# WiFiNode_CPU2_R00.net
KiCad netlist of a schematic drawn in Altium Designer
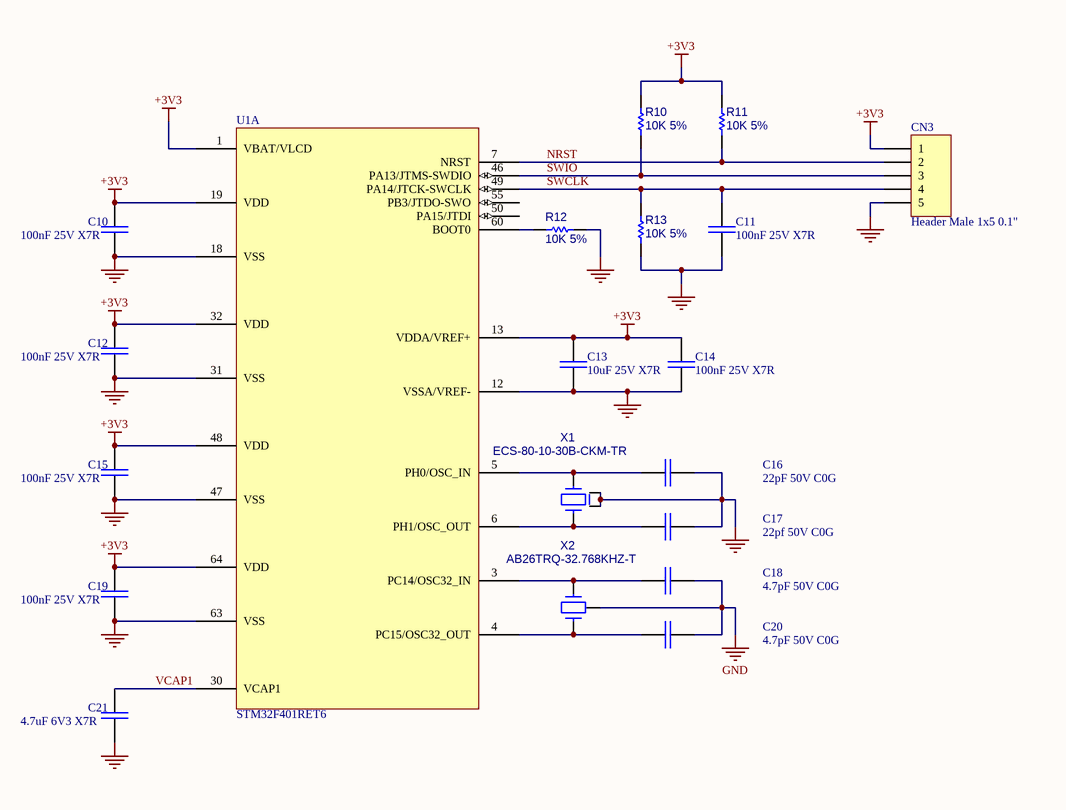
[diagram p0: WiFiNode_CPU2_R00.SchDoc]

(export (version "E")
  (design (tool "Eeschema 10.0.6"))
  (components
    (comp (ref "C10")
      (value "100nF 25V X7R")
      (footprint "C_0805")
      (description "Ceramic Capacitor")
      (libsource (lib "WiFiNode_R00") (part "Ceramic capacitor"))
    )
    (comp (ref "C11")
      (value "100nF 25V X7R")
      (footprint "C_0805")
      (description "Ceramic Capacitor")
      (libsource (lib "WiFiNode_R00") (part "Ceramic capacitor"))
    )
    (comp (ref "C12")
      (value "100nF 25V X7R")
      (footprint "C_0805")
      (description "Ceramic Capacitor")
      (libsource (lib "WiFiNode_R00") (part "Ceramic capacitor"))
    )
    (comp (ref "C13")
      (value "10uF 25V X7R")
      (footprint "C_0805")
      (description "Ceramic Capacitor")
      (libsource (lib "WiFiNode_R00") (part "Ceramic capacitor"))
    )
    (comp (ref "C14")
      (value "100nF 25V X7R")
      (footprint "C_0805")
      (description "Ceramic Capacitor")
      (libsource (lib "WiFiNode_R00") (part "Ceramic capacitor"))
    )
    (comp (ref "C15")
      (value "100nF 25V X7R")
      (footprint "C_0805")
      (description "Ceramic Capacitor")
      (libsource (lib "WiFiNode_R00") (part "Ceramic capacitor"))
    )
    (comp (ref "C16")
      (value "22pF 50V C0G")
      (footprint "C_0805")
      (description "Ceramic Capacitor")
      (libsource (lib "WiFiNode_R00") (part "Ceramic capacitor"))
    )
    (comp (ref "C17")
      (value "22pf 50V C0G")
      (footprint "C_0805")
      (description "Ceramic Capacitor")
      (libsource (lib "WiFiNode_R00") (part "Ceramic capacitor"))
    )
    (comp (ref "C18")
      (value "4.7pF 50V C0G")
      (footprint "C_0805")
      (description "Ceramic Capacitor")
      (libsource (lib "WiFiNode_R00") (part "Ceramic capacitor"))
    )
    (comp (ref "C19")
      (value "100nF 25V X7R")
      (footprint "C_0805")
      (description "Ceramic Capacitor")
      (libsource (lib "WiFiNode_R00") (part "Ceramic capacitor"))
    )
    (comp (ref "C20")
      (value "4.7pF 50V C0G")
      (footprint "C_0805")
      (description "Ceramic Capacitor")
      (libsource (lib "WiFiNode_R00") (part "Ceramic capacitor"))
    )
    (comp (ref "C21")
      (value "4.7uF 6V3 X7R")
      (footprint "C_0805")
      (description "Ceramic Capacitor")
      (libsource (lib "WiFiNode_R00") (part "Ceramic capacitor"))
    )
    (comp (ref "CN3")
      (value "Header Male 1x5 0.1\"")
      (footprint "Header_M_1x5_0.1\"")
      (description "Connector Generic 5 Vias")
      (libsource (lib "WiFiNode_R00") (part "CONN_05P"))
    )
    (comp (ref "R10")
      (value "10K 5%")
      (footprint "R_0805")
      (description "Resistor")
      (libsource (lib "WiFiNode_R00") (part "Res1"))
    )
    (comp (ref "R11")
      (value "10K 5%")
      (footprint "R_0805")
      (description "Resistor")
      (libsource (lib "WiFiNode_R00") (part "Res1"))
    )
    (comp (ref "R12")
      (value "10K 5%")
      (footprint "R_0805")
      (description "Resistor")
      (libsource (lib "WiFiNode_R00") (part "Res1"))
    )
    (comp (ref "R13")
      (value "10K 5%")
      (footprint "R_0805")
      (description "Resistor")
      (libsource (lib "WiFiNode_R00") (part "Res1"))
    )
    (comp (ref "U1")
      (value "STM32F401RET6")
      (footprint "LQFP_64")
      (libsource (lib "WiFiNode_R00") (part "STM32F401RE"))
    )
    (comp (ref "X1")
      (value "ECS-80-10-30B-CKM-TR")
      (footprint "ABM3C")
      (description "Crystal 4 Vias + GND")
      (libsource (lib "WiFiNode_R00") (part "CRYSTAL_4P"))
    )
    (comp (ref "X2")
      (value "AB26TRQ-32.768KHZ-T")
      (footprint "AB26TQF")
      (description "Crystal 2 Vias + GND")
      (libsource (lib "WiFiNode_R00") (part "CRYSTAL 3P"))
    )
  )
  (nets
    (net (code "1") (name "+3V3") (class "Default")
      (node (ref "C10") (pin "1") (pinfunction "1_1") (pintype "passive"))
      (node (ref "C12") (pin "1") (pinfunction "1_1") (pintype "passive"))
      (node (ref "C13") (pin "1") (pinfunction "1_1") (pintype "passive"))
      (node (ref "C14") (pin "1") (pinfunction "1_1") (pintype "passive"))
      (node (ref "C15") (pin "1") (pinfunction "1_1") (pintype "passive"))
      (node (ref "C19") (pin "1") (pinfunction "1_1") (pintype "passive"))
      (node (ref "CN3") (pin "1") (pinfunction "1_1") (pintype "passive"))
      (node (ref "R10") (pin "1") (pinfunction "1_1") (pintype "passive"))
      (node (ref "R11") (pin "1") (pinfunction "1_1") (pintype "passive"))
      (node (ref "U1") (pin "1") (pinfunction "VBAT/VLCD_1") (pintype "passive"))
      (node (ref "U1") (pin "13") (pinfunction "VDDA/VREF+_13") (pintype "passive"))
      (node (ref "U1") (pin "19") (pinfunction "VDD_19") (pintype "passive"))
      (node (ref "U1") (pin "32") (pinfunction "VDD_32") (pintype "passive"))
      (node (ref "U1") (pin "48") (pinfunction "VDD_48") (pintype "passive"))
      (node (ref "U1") (pin "64") (pinfunction "VDD_64") (pintype "passive"))
    )
    (net (code "2") (name "/NRST") (class "Default")
      (node (ref "CN3") (pin "2") (pinfunction "2_2") (pintype "passive"))
      (node (ref "R11") (pin "2") (pinfunction "2_2") (pintype "passive"))
      (node (ref "U1") (pin "7") (pinfunction "NRST_7") (pintype "passive"))
    )
    (net (code "3") (name "/SWCLK") (class "Default")
      (node (ref "C11") (pin "1") (pinfunction "1_1") (pintype "passive"))
      (node (ref "CN3") (pin "4") (pinfunction "4_4") (pintype "passive"))
      (node (ref "R13") (pin "1") (pinfunction "1_1") (pintype "passive"))
      (node (ref "U1") (pin "49") (pinfunction "PA14/JTCK-SWCLK_49") (pintype "bidirectional"))
    )
    (net (code "4") (name "/SWIO") (class "Default")
      (node (ref "CN3") (pin "3") (pinfunction "3_3") (pintype "passive"))
      (node (ref "R10") (pin "2") (pinfunction "2_2") (pintype "passive"))
      (node (ref "U1") (pin "46") (pinfunction "PA13/JTMS-SWDIO_46") (pintype "bidirectional"))
    )
    (net (code "5") (name "/VCAP1") (class "Default")
      (node (ref "C21") (pin "1") (pinfunction "1_1") (pintype "passive"))
      (node (ref "U1") (pin "30") (pinfunction "VCAP1_30") (pintype "passive"))
    )
    (net (code "6") (name "GND") (class "Default")
      (node (ref "C10") (pin "2") (pinfunction "2_2") (pintype "passive"))
      (node (ref "C11") (pin "2") (pinfunction "2_2") (pintype "passive"))
      (node (ref "C12") (pin "2") (pinfunction "2_2") (pintype "passive"))
      (node (ref "C13") (pin "2") (pinfunction "2_2") (pintype "passive"))
      (node (ref "C14") (pin "2") (pinfunction "2_2") (pintype "passive"))
      (node (ref "C15") (pin "2") (pinfunction "2_2") (pintype "passive"))
      (node (ref "C16") (pin "2") (pinfunction "2_2") (pintype "passive"))
      (node (ref "C17") (pin "2") (pinfunction "2_2") (pintype "passive"))
      (node (ref "C18") (pin "2") (pinfunction "2_2") (pintype "passive"))
      (node (ref "C19") (pin "2") (pinfunction "2_2") (pintype "passive"))
      (node (ref "C20") (pin "2") (pinfunction "2_2") (pintype "passive"))
      (node (ref "C21") (pin "2") (pinfunction "2_2") (pintype "passive"))
      (node (ref "CN3") (pin "5") (pinfunction "5_5") (pintype "passive"))
      (node (ref "R12") (pin "1") (pinfunction "1_1") (pintype "passive"))
      (node (ref "R13") (pin "2") (pinfunction "2_2") (pintype "passive"))
      (node (ref "U1") (pin "12") (pinfunction "VSSA/VREF-_12") (pintype "passive"))
      (node (ref "U1") (pin "18") (pinfunction "VSS_18") (pintype "passive"))
      (node (ref "U1") (pin "31") (pinfunction "VSS_31") (pintype "passive"))
      (node (ref "U1") (pin "47") (pinfunction "VSS_47") (pintype "passive"))
      (node (ref "U1") (pin "63") (pinfunction "VSS_63") (pintype "passive"))
      (node (ref "X1") (pin "2") (pinfunction "2_2") (pintype "passive"))
      (node (ref "X1") (pin "4") (pinfunction "4_4") (pintype "passive"))
      (node (ref "X2") (pin "3") (pinfunction "3_3") (pintype "passive"))
    )
    (net (code "7") (name "Net-(U1A-BOOT0)") (class "Default")
      (node (ref "R12") (pin "2") (pinfunction "2_2") (pintype "passive"))
      (node (ref "U1") (pin "60") (pinfunction "BOOT0_60") (pintype "passive"))
    )
    (net (code "8") (name "Net-(U1A-PC14{slash}OSC32_IN)") (class "Default")
      (node (ref "C18") (pin "1") (pinfunction "1_1") (pintype "passive"))
      (node (ref "U1") (pin "3") (pinfunction "PC14/OSC32_IN_3") (pintype "passive"))
      (node (ref "X2") (pin "2") (pinfunction "2_2") (pintype "passive"))
    )
    (net (code "9") (name "Net-(U1A-PC15{slash}OSC32_OUT)") (class "Default")
      (node (ref "C20") (pin "1") (pinfunction "1_1") (pintype "passive"))
      (node (ref "U1") (pin "4") (pinfunction "PC15/OSC32_OUT_4") (pintype "passive"))
      (node (ref "X2") (pin "1") (pinfunction "1_1") (pintype "passive"))
    )
    (net (code "10") (name "Net-(U1A-PH0{slash}OSC_IN)") (class "Default")
      (node (ref "C16") (pin "1") (pinfunction "1_1") (pintype "passive"))
      (node (ref "U1") (pin "5") (pinfunction "PH0/OSC_IN_5") (pintype "passive"))
      (node (ref "X1") (pin "1") (pinfunction "1_1") (pintype "passive"))
    )
    (net (code "11") (name "Net-(U1A-PH1{slash}OSC_OUT)") (class "Default")
      (node (ref "C17") (pin "1") (pinfunction "1_1") (pintype "passive"))
      (node (ref "U1") (pin "6") (pinfunction "PH1/OSC_OUT_6") (pintype "passive"))
      (node (ref "X1") (pin "3") (pinfunction "3_3") (pintype "passive"))
    )
    (net (code "12") (name "unconnected-(U1A-PA15{slash}JTDI-Pad50)") (class "Default")
      (node (ref "U1") (pin "50") (pinfunction "PA15/JTDI_50") (pintype "bidirectional"))
    )
    (net (code "13") (name "unconnected-(U1A-PB3{slash}JTDO-SWO-Pad55)") (class "Default")
      (node (ref "U1") (pin "55") (pinfunction "PB3/JTDO-SWO_55") (pintype "bidirectional"))
    )
  )
)
